# E-InkSmartMonitor.net
KiCad netlist of a schematic drawn in EAGLE
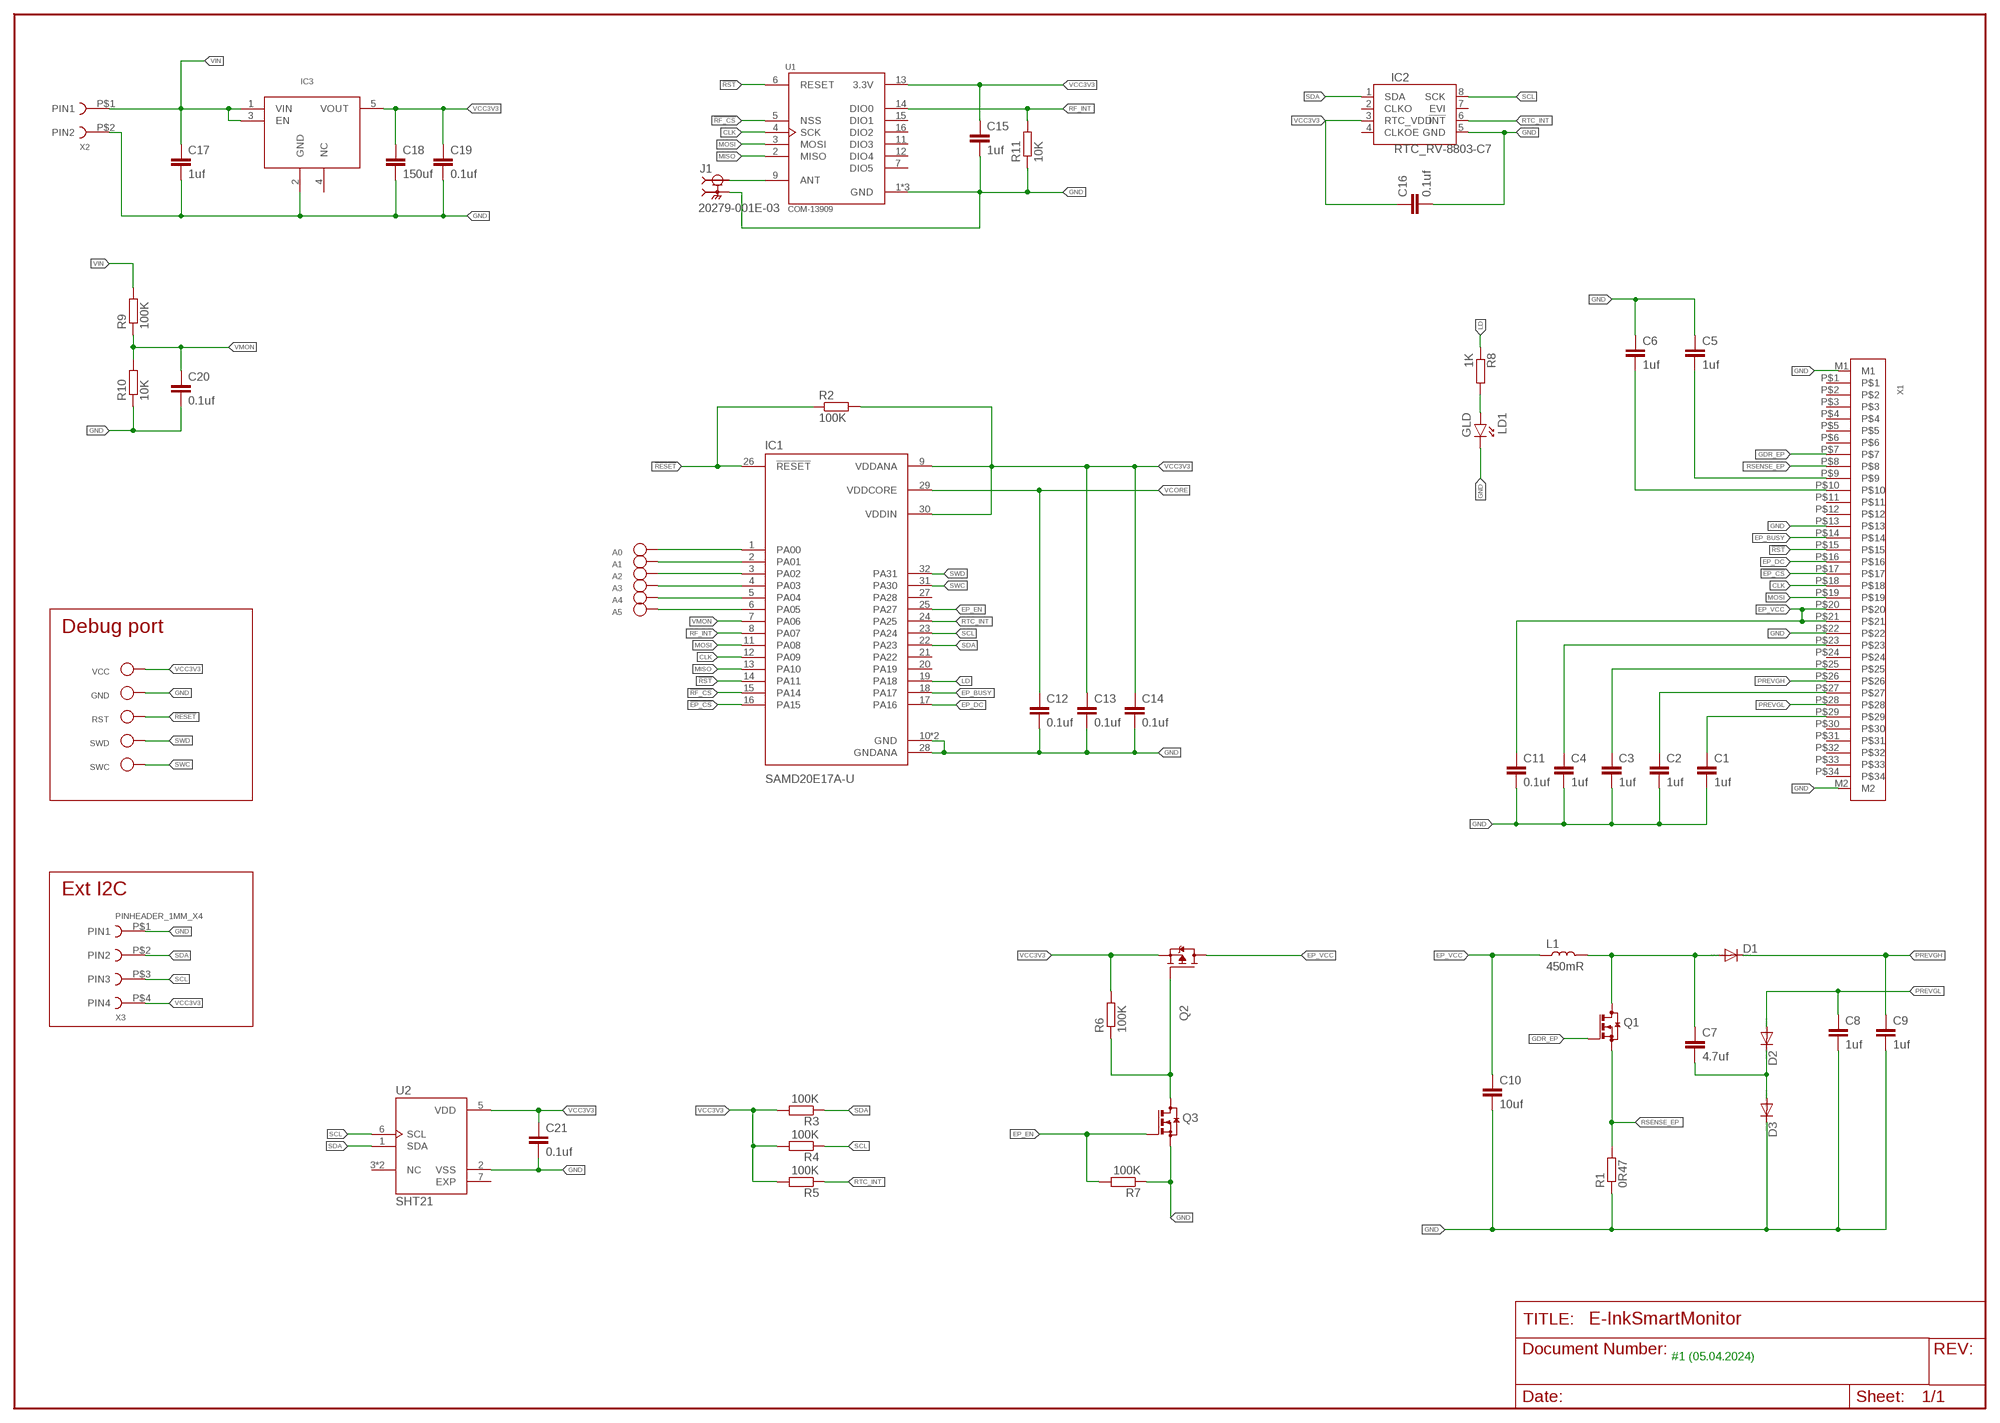
[diagram p0: schematic, sheet 1]

(export (version "E")
  (design (tool "Eeschema 10.0.6"))
  (components
    (comp (ref "A0")
      (value "TEST_POINT_D2MM")
      (footprint "eagle-import:TP")
      (libsource (lib "eagle-import") (part "TEST_POINT_D2MM"))
    )
    (comp (ref "A1")
      (value "TEST_POINT_D2MM")
      (footprint "eagle-import:TP")
      (libsource (lib "eagle-import") (part "TEST_POINT_D2MM"))
    )
    (comp (ref "A2")
      (value "TEST_POINT_D2MM")
      (footprint "eagle-import:TP")
      (libsource (lib "eagle-import") (part "TEST_POINT_D2MM"))
    )
    (comp (ref "A3")
      (value "TEST_POINT_D2MM")
      (footprint "eagle-import:TP")
      (libsource (lib "eagle-import") (part "TEST_POINT_D2MM"))
    )
    (comp (ref "A4")
      (value "TEST_POINT_D2MM")
      (footprint "eagle-import:TP")
      (libsource (lib "eagle-import") (part "TEST_POINT_D2MM"))
    )
    (comp (ref "A5")
      (value "TEST_POINT_D2MM")
      (footprint "eagle-import:TP")
      (libsource (lib "eagle-import") (part "TEST_POINT_D2MM"))
    )
    (comp (ref "C1")
      (value "1uf")
      (footprint "eagle-import:0805")
      (libsource (lib "eagle-import") (part "SMD_C0805"))
    )
    (comp (ref "C2")
      (value "1uf")
      (footprint "eagle-import:0805")
      (libsource (lib "eagle-import") (part "SMD_C0805"))
    )
    (comp (ref "C3")
      (value "1uf")
      (footprint "eagle-import:0805")
      (libsource (lib "eagle-import") (part "SMD_C0805"))
    )
    (comp (ref "C4")
      (value "1uf")
      (footprint "eagle-import:0805")
      (libsource (lib "eagle-import") (part "SMD_C0805"))
    )
    (comp (ref "C5")
      (value "1uf")
      (footprint "eagle-import:0805")
      (libsource (lib "eagle-import") (part "SMD_C0805"))
    )
    (comp (ref "C6")
      (value "1uf")
      (footprint "eagle-import:0805")
      (libsource (lib "eagle-import") (part "SMD_C0805"))
    )
    (comp (ref "C7")
      (value "4.7uf")
      (footprint "eagle-import:0805")
      (libsource (lib "eagle-import") (part "SMD_C0805"))
    )
    (comp (ref "C8")
      (value "1uf")
      (footprint "eagle-import:0805")
      (libsource (lib "eagle-import") (part "SMD_C0805"))
    )
    (comp (ref "C9")
      (value "1uf")
      (footprint "eagle-import:0805")
      (libsource (lib "eagle-import") (part "SMD_C0805"))
    )
    (comp (ref "C10")
      (value "10uf")
      (footprint "eagle-import:0805")
      (libsource (lib "eagle-import") (part "SMD_C0805"))
    )
    (comp (ref "C11")
      (value "0.1uf")
      (footprint "eagle-import:0603")
      (libsource (lib "eagle-import") (part "SMD_C0603"))
    )
    (comp (ref "C12")
      (value "0.1uf")
      (footprint "eagle-import:0603")
      (libsource (lib "eagle-import") (part "SMD_C0603"))
    )
    (comp (ref "C13")
      (value "0.1uf")
      (footprint "eagle-import:0603")
      (libsource (lib "eagle-import") (part "SMD_C0603"))
    )
    (comp (ref "C14")
      (value "0.1uf")
      (footprint "eagle-import:0603")
      (libsource (lib "eagle-import") (part "SMD_C0603"))
    )
    (comp (ref "C15")
      (value "1uf")
      (footprint "eagle-import:0805")
      (libsource (lib "eagle-import") (part "SMD_C0805"))
    )
    (comp (ref "C16")
      (value "0.1uf")
      (footprint "eagle-import:0603")
      (libsource (lib "eagle-import") (part "SMD_C0603"))
    )
    (comp (ref "C17")
      (value "1uf")
      (footprint "eagle-import:0805")
      (libsource (lib "eagle-import") (part "SMD_C0805"))
    )
    (comp (ref "C18")
      (value "150uf")
      (footprint "eagle-import:0805")
      (libsource (lib "eagle-import") (part "SMD_C0805"))
    )
    (comp (ref "C19")
      (value "0.1uf")
      (footprint "eagle-import:0603")
      (libsource (lib "eagle-import") (part "SMD_C0603"))
    )
    (comp (ref "C20")
      (value "0.1uf")
      (footprint "eagle-import:0603")
      (libsource (lib "eagle-import") (part "SMD_C0603"))
    )
    (comp (ref "C21")
      (value "0.1uf")
      (footprint "eagle-import:0603")
      (libsource (lib "eagle-import") (part "SMD_C0603"))
    )
    (comp (ref "D1")
      (value "DIODE-SOD323-R")
      (footprint "eagle-import:SOD323-R")
      (libsource (lib "eagle-import") (part "DIODE-SOD323-R"))
    )
    (comp (ref "D2")
      (value "DIODE-SOD323-R")
      (footprint "eagle-import:SOD323-R")
      (libsource (lib "eagle-import") (part "DIODE-SOD323-R"))
    )
    (comp (ref "D3")
      (value "DIODE-SOD323-R")
      (footprint "eagle-import:SOD323-R")
      (libsource (lib "eagle-import") (part "DIODE-SOD323-R"))
    )
    (comp (ref "GND")
      (value "TEST_POINT_D2MM")
      (footprint "eagle-import:TP")
      (libsource (lib "eagle-import") (part "TEST_POINT_D2MM"))
    )
    (comp (ref "IC1")
      (value "SAMD20E17A-U")
      (footprint "eagle-import:MLF32-TH")
      (libsource (lib "eagle-import") (part "SAMD20E17A-U"))
    )
    (comp (ref "IC2")
      (value "RTC_RV-8803-C7")
      (footprint "eagle-import:C7_RTC")
      (libsource (lib "eagle-import") (part "RTC_RV-8803-C7"))
    )
    (comp (ref "IC3")
      (value "LDO_3.3V_SOT23(5)")
      (footprint "eagle-import:SOT-23(5)")
      (libsource (lib "eagle-import") (part "LDO_3.3V_SOT23(5)"))
    )
    (comp (ref "J1")
      (value "20279-001E-03")
      (footprint "eagle-import:IPEX_20279-001E-03")
      (fields (field (name "MF") "I-PEX"))
      (libsource (lib "eagle-import") (part "20279-001E-03"))
    )
    (comp (ref "L1")
      (value "450mR")
      (footprint "eagle-import:3232")
      (libsource (lib "eagle-import") (part "SMD_L3232"))
    )
    (comp (ref "LD1")
      (value "GLD")
      (footprint "eagle-import:0603_P")
      (libsource (lib "eagle-import") (part "LED0603"))
    )
    (comp (ref "Q1")
      (value "BSS123SOT-23-3")
      (footprint "eagle-import:SOT-23(3)")
      (libsource (lib "eagle-import") (part "BSS123SOT-23-3"))
    )
    (comp (ref "Q2")
      (value "P_CH_SOT23SOT-23-3")
      (footprint "eagle-import:SOT-23(3)")
      (libsource (lib "eagle-import") (part "P_CH_SOT23SOT-23-3"))
    )
    (comp (ref "Q3")
      (value "BSS123SOT-23-3")
      (footprint "eagle-import:SOT-23(3)")
      (libsource (lib "eagle-import") (part "BSS123SOT-23-3"))
    )
    (comp (ref "R1")
      (value "0R47")
      (footprint "eagle-import:0603")
      (libsource (lib "eagle-import") (part "SMD_R0603"))
    )
    (comp (ref "R2")
      (value "100K")
      (footprint "eagle-import:0603")
      (libsource (lib "eagle-import") (part "SMD_R0603"))
    )
    (comp (ref "R3")
      (value "100K")
      (footprint "eagle-import:0603")
      (libsource (lib "eagle-import") (part "SMD_R0603"))
    )
    (comp (ref "R4")
      (value "100K")
      (footprint "eagle-import:0603")
      (libsource (lib "eagle-import") (part "SMD_R0603"))
    )
    (comp (ref "R5")
      (value "100K")
      (footprint "eagle-import:0603")
      (libsource (lib "eagle-import") (part "SMD_R0603"))
    )
    (comp (ref "R6")
      (value "100K")
      (footprint "eagle-import:0603")
      (libsource (lib "eagle-import") (part "SMD_R0603"))
    )
    (comp (ref "R7")
      (value "100K")
      (footprint "eagle-import:0603")
      (libsource (lib "eagle-import") (part "SMD_R0603"))
    )
    (comp (ref "R8")
      (value "1K")
      (footprint "eagle-import:0603")
      (libsource (lib "eagle-import") (part "SMD_R0603"))
    )
    (comp (ref "R9")
      (value "100K")
      (footprint "eagle-import:0603")
      (libsource (lib "eagle-import") (part "SMD_R0603"))
    )
    (comp (ref "R10")
      (value "10K")
      (footprint "eagle-import:0603")
      (libsource (lib "eagle-import") (part "SMD_R0603"))
    )
    (comp (ref "R11")
      (value "10K")
      (footprint "eagle-import:0603")
      (libsource (lib "eagle-import") (part "SMD_R0603"))
    )
    (comp (ref "RST")
      (value "TEST_POINT_D2MM")
      (footprint "eagle-import:TP")
      (libsource (lib "eagle-import") (part "TEST_POINT_D2MM"))
    )
    (comp (ref "SWC")
      (value "TEST_POINT_D2MM")
      (footprint "eagle-import:TP")
      (libsource (lib "eagle-import") (part "TEST_POINT_D2MM"))
    )
    (comp (ref "SWD")
      (value "TEST_POINT_D2MM")
      (footprint "eagle-import:TP")
      (libsource (lib "eagle-import") (part "TEST_POINT_D2MM"))
    )
    (comp (ref "U1")
      (value "COM-13909")
      (footprint "eagle-import:MOD_COM-13909")
      (fields (field (name "MF") "HOPERF") (field (name "MP") "RFM69HCW-315S2"))
      (libsource (lib "eagle-import") (part "COM-13909"))
    )
    (comp (ref "U2")
      (value "SHT21")
      (footprint "eagle-import:XDCR_SHT21")
      (fields (field (name "MF") "Sensirion AG"))
      (libsource (lib "eagle-import") (part "SHT21"))
    )
    (comp (ref "VCC")
      (value "TEST_POINT_D2MM")
      (footprint "eagle-import:TP")
      (libsource (lib "eagle-import") (part "TEST_POINT_D2MM"))
    )
    (comp (ref "X1")
      (value "FFC_3405EINK")
      (footprint "eagle-import:FFC_3405EINK")
      (libsource (lib "eagle-import") (part "FFC_3405EINK"))
    )
    (comp (ref "X2")
      (value "PINHEADER_1MM_X22X_1MM_PIN")
      (footprint "eagle-import:PIN_1MM_X2")
      (libsource (lib "eagle-import") (part "PINHEADER_1MM_X22X_1MM_PIN"))
    )
    (comp (ref "X3")
      (value "PINHEADER_1MM_X4")
      (footprint "eagle-import:PIN_1MM_X4")
      (libsource (lib "eagle-import") (part "PINHEADER_1MM_X4"))
    )
  )
  (nets
    (net (code "1") (name "/~{EP_CS}") (class "Default")
      (node (ref "IC1") (pin "16") (pinfunction "PA15_16") (pintype "bidirectional"))
      (node (ref "X1") (pin "P$17") (pinfunction "P$17_P$17") (pintype "bidirectional"))
    )
    (net (code "2") (name "/~{RESET}") (class "Default")
      (node (ref "IC1") (pin "26") (pinfunction "~{RESET}_26") (pintype "input"))
      (node (ref "R2") (pin "1") (pinfunction "1_1") (pintype "passive"))
      (node (ref "RST") (pin "P$1") (pinfunction "1_P$1") (pintype "bidirectional"))
    )
    (net (code "3") (name "/~{RF_CS}") (class "Default")
      (node (ref "IC1") (pin "15") (pinfunction "PA14_15") (pintype "bidirectional"))
      (node (ref "U1") (pin "5") (pinfunction "NSS_5") (pintype "input"))
    )
    (net (code "4") (name "/~{RST}") (class "Default")
      (node (ref "IC1") (pin "14") (pinfunction "PA11_14") (pintype "bidirectional"))
      (node (ref "U1") (pin "6") (pinfunction "RESET_6") (pintype "bidirectional"))
      (node (ref "X1") (pin "P$15") (pinfunction "P$15_P$15") (pintype "bidirectional"))
    )
    (net (code "5") (name "CLK") (class "Default")
      (node (ref "IC1") (pin "12") (pinfunction "PA09_12") (pintype "bidirectional"))
      (node (ref "U1") (pin "4") (pinfunction "SCK_4") (pintype "input"))
      (node (ref "X1") (pin "P$18") (pinfunction "P$18_P$18") (pintype "bidirectional"))
    )
    (net (code "6") (name "EP_BUSY") (class "Default")
      (node (ref "IC1") (pin "18") (pinfunction "PA17_18") (pintype "bidirectional"))
      (node (ref "X1") (pin "P$14") (pinfunction "P$14_P$14") (pintype "bidirectional"))
    )
    (net (code "7") (name "EP_DC") (class "Default")
      (node (ref "IC1") (pin "17") (pinfunction "PA16_17") (pintype "bidirectional"))
      (node (ref "X1") (pin "P$16") (pinfunction "P$16_P$16") (pintype "bidirectional"))
    )
    (net (code "8") (name "EP_EN") (class "Default")
      (node (ref "IC1") (pin "25") (pinfunction "PA27_25") (pintype "bidirectional"))
      (node (ref "Q3") (pin "1") (pinfunction "G_1") (pintype "passive"))
      (node (ref "R7") (pin "2") (pinfunction "2_2") (pintype "passive"))
    )
    (net (code "9") (name "EP_VCC") (class "Default")
      (node (ref "C10") (pin "1") (pinfunction "1_1") (pintype "passive"))
      (node (ref "C11") (pin "1") (pinfunction "1_1") (pintype "passive"))
      (node (ref "L1") (pin "M") (pinfunction "1_M") (pintype "passive"))
      (node (ref "Q2") (pin "3") (pinfunction "D_3") (pintype "passive"))
      (node (ref "X1") (pin "P$20") (pinfunction "P$20_P$20") (pintype "bidirectional"))
      (node (ref "X1") (pin "P$21") (pinfunction "P$21_P$21") (pintype "bidirectional"))
    )
    (net (code "10") (name "GDR_EP") (class "Default")
      (node (ref "Q1") (pin "1") (pinfunction "G_1") (pintype "passive"))
      (node (ref "X1") (pin "P$7") (pinfunction "P$7_P$7") (pintype "bidirectional"))
    )
    (net (code "11") (name "GND") (class "Default")
      (node (ref "C1") (pin "2") (pinfunction "2_2") (pintype "passive"))
      (node (ref "C10") (pin "2") (pinfunction "2_2") (pintype "passive"))
      (node (ref "C11") (pin "2") (pinfunction "2_2") (pintype "passive"))
      (node (ref "C12") (pin "2") (pinfunction "2_2") (pintype "passive"))
      (node (ref "C13") (pin "2") (pinfunction "2_2") (pintype "passive"))
      (node (ref "C14") (pin "2") (pinfunction "2_2") (pintype "passive"))
      (node (ref "C15") (pin "2") (pinfunction "2_2") (pintype "passive"))
      (node (ref "C16") (pin "2") (pinfunction "2_2") (pintype "passive"))
      (node (ref "C17") (pin "2") (pinfunction "2_2") (pintype "passive"))
      (node (ref "C18") (pin "2") (pinfunction "2_2") (pintype "passive"))
      (node (ref "C19") (pin "2") (pinfunction "2_2") (pintype "passive"))
      (node (ref "C2") (pin "2") (pinfunction "2_2") (pintype "passive"))
      (node (ref "C20") (pin "2") (pinfunction "2_2") (pintype "passive"))
      (node (ref "C21") (pin "2") (pinfunction "2_2") (pintype "passive"))
      (node (ref "C3") (pin "2") (pinfunction "2_2") (pintype "passive"))
      (node (ref "C4") (pin "2") (pinfunction "2_2") (pintype "passive"))
      (node (ref "C5") (pin "1") (pinfunction "1_1") (pintype "passive"))
      (node (ref "C6") (pin "1") (pinfunction "1_1") (pintype "passive"))
      (node (ref "C8") (pin "2") (pinfunction "2_2") (pintype "passive"))
      (node (ref "C9") (pin "2") (pinfunction "2_2") (pintype "passive"))
      (node (ref "D3") (pin "C") (pinfunction "C_C") (pintype "passive"))
      (node (ref "GND") (pin "P$1") (pinfunction "1_P$1") (pintype "bidirectional"))
      (node (ref "IC1") (pin "10") (pinfunction "GND_10") (pintype "power_in"))
      (node (ref "IC1") (pin "28") (pinfunction "GNDANA_28") (pintype "power_in"))
      (node (ref "IC1") (pin "TH") (pinfunction "GND_TH") (pintype "power_in"))
      (node (ref "IC2") (pin "5") (pinfunction "GND_5") (pintype "bidirectional"))
      (node (ref "IC3") (pin "2") (pinfunction "GND_2") (pintype "bidirectional"))
      (node (ref "J1") (pin "2") (pinfunction "GND_2") (pintype "passive"))
      (node (ref "J1") (pin "3") (pinfunction "GND_3") (pintype "passive"))
      (node (ref "LD1") (pin "1") (pinfunction "K_1") (pintype "bidirectional"))
      (node (ref "Q3") (pin "2") (pinfunction "S_2") (pintype "passive"))
      (node (ref "R1") (pin "1") (pinfunction "1_1") (pintype "passive"))
      (node (ref "R10") (pin "1") (pinfunction "1_1") (pintype "passive"))
      (node (ref "R11") (pin "1") (pinfunction "1_1") (pintype "passive"))
      (node (ref "R7") (pin "1") (pinfunction "1_1") (pintype "passive"))
      (node (ref "U1") (pin "1") (pinfunction "GND_1") (pintype "power_in"))
      (node (ref "U1") (pin "10") (pinfunction "GND_10") (pintype "power_in"))
      (node (ref "U1") (pin "8") (pinfunction "GND_8") (pintype "power_in"))
      (node (ref "U2") (pin "2") (pinfunction "VSS_2") (pintype "power_in"))
      (node (ref "X1") (pin "M1") (pinfunction "M1_M1") (pintype "bidirectional"))
      (node (ref "X1") (pin "M2") (pinfunction "M2_M2") (pintype "bidirectional"))
      (node (ref "X1") (pin "P$13") (pinfunction "P$13_P$13") (pintype "bidirectional"))
      (node (ref "X1") (pin "P$22") (pinfunction "P$22_P$22") (pintype "bidirectional"))
      (node (ref "X2") (pin "P$2") (pinfunction "PIN2_P$2") (pintype "bidirectional"))
      (node (ref "X3") (pin "P$1") (pinfunction "PIN1_P$1") (pintype "bidirectional"))
    )
    (net (code "12") (name "LD") (class "Default")
      (node (ref "IC1") (pin "19") (pinfunction "PA18_19") (pintype "bidirectional"))
      (node (ref "R8") (pin "1") (pinfunction "1_1") (pintype "passive"))
    )
    (net (code "13") (name "MISO") (class "Default")
      (node (ref "IC1") (pin "13") (pinfunction "PA10_13") (pintype "bidirectional"))
      (node (ref "U1") (pin "2") (pinfunction "MISO_2") (pintype "input"))
    )
    (net (code "14") (name "MOSI") (class "Default")
      (node (ref "IC1") (pin "11") (pinfunction "PA08_11") (pintype "bidirectional"))
      (node (ref "U1") (pin "3") (pinfunction "MOSI_3") (pintype "output"))
      (node (ref "X1") (pin "P$19") (pinfunction "P$19_P$19") (pintype "bidirectional"))
    )
    (net (code "15") (name "Net-(A0-1)") (class "Default")
      (node (ref "A0") (pin "P$1") (pinfunction "1_P$1") (pintype "bidirectional"))
      (node (ref "IC1") (pin "1") (pinfunction "PA00_1") (pintype "bidirectional"))
    )
    (net (code "16") (name "Net-(A1-1)") (class "Default")
      (node (ref "A1") (pin "P$1") (pinfunction "1_P$1") (pintype "bidirectional"))
      (node (ref "IC1") (pin "2") (pinfunction "PA01_2") (pintype "bidirectional"))
    )
    (net (code "17") (name "Net-(A2-1)") (class "Default")
      (node (ref "A2") (pin "P$1") (pinfunction "1_P$1") (pintype "bidirectional"))
      (node (ref "IC1") (pin "3") (pinfunction "PA02_3") (pintype "bidirectional"))
    )
    (net (code "18") (name "Net-(A3-1)") (class "Default")
      (node (ref "A3") (pin "P$1") (pinfunction "1_P$1") (pintype "bidirectional"))
      (node (ref "IC1") (pin "4") (pinfunction "PA03_4") (pintype "bidirectional"))
    )
    (net (code "19") (name "Net-(A4-1)") (class "Default")
      (node (ref "A4") (pin "P$1") (pinfunction "1_P$1") (pintype "bidirectional"))
      (node (ref "IC1") (pin "5") (pinfunction "PA04_5") (pintype "bidirectional"))
    )
    (net (code "20") (name "Net-(A5-1)") (class "Default")
      (node (ref "A5") (pin "P$1") (pinfunction "1_P$1") (pintype "bidirectional"))
      (node (ref "IC1") (pin "6") (pinfunction "PA05_6") (pintype "bidirectional"))
    )
    (net (code "21") (name "Net-(C1-Pad1)") (class "Default")
      (node (ref "C1") (pin "1") (pinfunction "1_1") (pintype "passive"))
      (node (ref "X1") (pin "P$29") (pinfunction "P$29_P$29") (pintype "bidirectional"))
    )
    (net (code "22") (name "Net-(C2-Pad1)") (class "Default")
      (node (ref "C2") (pin "1") (pinfunction "1_1") (pintype "passive"))
      (node (ref "X1") (pin "P$27") (pinfunction "P$27_P$27") (pintype "bidirectional"))
    )
    (net (code "23") (name "Net-(C3-Pad1)") (class "Default")
      (node (ref "C3") (pin "1") (pinfunction "1_1") (pintype "passive"))
      (node (ref "X1") (pin "P$25") (pinfunction "P$25_P$25") (pintype "bidirectional"))
    )
    (net (code "24") (name "Net-(C4-Pad1)") (class "Default")
      (node (ref "C4") (pin "1") (pinfunction "1_1") (pintype "passive"))
      (node (ref "X1") (pin "P$23") (pinfunction "P$23_P$23") (pintype "bidirectional"))
    )
    (net (code "25") (name "Net-(C5-Pad2)") (class "Default")
      (node (ref "C5") (pin "2") (pinfunction "2_2") (pintype "passive"))
      (node (ref "X1") (pin "P$9") (pinfunction "P$9_P$9") (pintype "bidirectional"))
    )
    (net (code "26") (name "Net-(C6-Pad2)") (class "Default")
      (node (ref "C6") (pin "2") (pinfunction "2_2") (pintype "passive"))
      (node (ref "X1") (pin "P$10") (pinfunction "P$10_P$10") (pintype "bidirectional"))
    )
    (net (code "27") (name "Net-(C7-Pad2)") (class "Default")
      (node (ref "C7") (pin "2") (pinfunction "2_2") (pintype "passive"))
      (node (ref "D2") (pin "C") (pinfunction "C_C") (pintype "passive"))
      (node (ref "D3") (pin "A") (pinfunction "A_A") (pintype "passive"))
    )
    (net (code "28") (name "Net-(J1-SIG)") (class "Default")
      (node (ref "J1") (pin "1") (pinfunction "SIG_1") (pintype "passive"))
      (node (ref "U1") (pin "9") (pinfunction "ANT_9") (pintype "bidirectional"))
    )
    (net (code "29") (name "Net-(L1-2)") (class "Default")
      (node (ref "C7") (pin "1") (pinfunction "1_1") (pintype "passive"))
      (node (ref "D1") (pin "A") (pinfunction "A_A") (pintype "passive"))
      (node (ref "L1") (pin "P") (pinfunction "2_P") (pintype "passive"))
      (node (ref "Q1") (pin "3") (pinfunction "D_3") (pintype "passive"))
    )
    (net (code "30") (name "Net-(LD1-A)") (class "Default")
      (node (ref "LD1") (pin "2") (pinfunction "A_2") (pintype "bidirectional"))
      (node (ref "R8") (pin "2") (pinfunction "2_2") (pintype "passive"))
    )
    (net (code "31") (name "Net-(Q2-G)") (class "Default")
      (node (ref "Q2") (pin "1") (pinfunction "G_1") (pintype "passive"))
      (node (ref "Q3") (pin "3") (pinfunction "D_3") (pintype "passive"))
      (node (ref "R6") (pin "1") (pinfunction "1_1") (pintype "passive"))
    )
    (net (code "32") (name "PREVGH") (class "Default")
      (node (ref "C9") (pin "1") (pinfunction "1_1") (pintype "passive"))
      (node (ref "D1") (pin "C") (pinfunction "C_C") (pintype "passive"))
      (node (ref "X1") (pin "P$26") (pinfunction "P$26_P$26") (pintype "bidirectional"))
    )
    (net (code "33") (name "PREVGL") (class "Default")
      (node (ref "C8") (pin "1") (pinfunction "1_1") (pintype "passive"))
      (node (ref "D2") (pin "A") (pinfunction "A_A") (pintype "passive"))
      (node (ref "X1") (pin "P$28") (pinfunction "P$28_P$28") (pintype "bidirectional"))
    )
    (net (code "34") (name "RF_INT") (class "Default")
      (node (ref "IC1") (pin "8") (pinfunction "PA07_8") (pintype "bidirectional"))
      (node (ref "R11") (pin "2") (pinfunction "2_2") (pintype "passive"))
      (node (ref "U1") (pin "14") (pinfunction "DIO0_14") (pintype "bidirectional"))
    )
    (net (code "35") (name "RSENSE_EP") (class "Default")
      (node (ref "Q1") (pin "2") (pinfunction "S_2") (pintype "passive"))
      (node (ref "R1") (pin "2") (pinfunction "2_2") (pintype "passive"))
      (node (ref "X1") (pin "P$8") (pinfunction "P$8_P$8") (pintype "bidirectional"))
    )
    (net (code "36") (name "RTC_INT") (class "Default")
      (node (ref "IC1") (pin "24") (pinfunction "PA25_24") (pintype "bidirectional"))
      (node (ref "IC2") (pin "6") (pinfunction "~{INT}_6") (pintype "bidirectional"))
      (node (ref "R5") (pin "1") (pinfunction "1_1") (pintype "passive"))
    )
    (net (code "37") (name "SCL") (class "Default")
      (node (ref "IC1") (pin "23") (pinfunction "PA24_23") (pintype "bidirectional"))
      (node (ref "IC2") (pin "8") (pinfunction "SCK_8") (pintype "bidirectional"))
      (node (ref "R4") (pin "1") (pinfunction "1_1") (pintype "passive"))
      (node (ref "U2") (pin "6") (pinfunction "SCL_6") (pintype "input"))
      (node (ref "X3") (pin "P$3") (pinfunction "PIN3_P$3") (pintype "bidirectional"))
    )
    (net (code "38") (name "SDA") (class "Default")
      (node (ref "IC1") (pin "22") (pinfunction "PA23_22") (pintype "bidirectional"))
      (node (ref "IC2") (pin "1") (pinfunction "SDA_1") (pintype "bidirectional"))
      (node (ref "R3") (pin "1") (pinfunction "1_1") (pintype "passive"))
      (node (ref "U2") (pin "1") (pinfunction "SDA_1") (pintype "bidirectional"))
      (node (ref "X3") (pin "P$2") (pinfunction "PIN2_P$2") (pintype "bidirectional"))
    )
    (net (code "39") (name "SWC") (class "Default")
      (node (ref "IC1") (pin "31") (pinfunction "PA30_31") (pintype "bidirectional"))
      (node (ref "SWC") (pin "P$1") (pinfunction "1_P$1") (pintype "bidirectional"))
    )
    (net (code "40") (name "SWD") (class "Default")
      (node (ref "IC1") (pin "32") (pinfunction "PA31_32") (pintype "bidirectional"))
      (node (ref "SWD") (pin "P$1") (pinfunction "1_P$1") (pintype "bidirectional"))
    )
    (net (code "41") (name "VCC3V3") (class "Default")
      (node (ref "C13") (pin "1") (pinfunction "1_1") (pintype "passive"))
      (node (ref "C14") (pin "1") (pinfunction "1_1") (pintype "passive"))
      (node (ref "C15") (pin "1") (pinfunction "1_1") (pintype "passive"))
      (node (ref "C16") (pin "1") (pinfunction "1_1") (pintype "passive"))
      (node (ref "C18") (pin "1") (pinfunction "1_1") (pintype "passive"))
      (node (ref "C19") (pin "1") (pinfunction "1_1") (pintype "passive"))
      (node (ref "C21") (pin "1") (pinfunction "1_1") (pintype "passive"))
      (node (ref "IC1") (pin "30") (pinfunction "VDDIN_30") (pintype "power_in"))
      (node (ref "IC1") (pin "9") (pinfunction "VDDANA_9") (pintype "power_in"))
      (node (ref "IC2") (pin "3") (pinfunction "RTC_VDD_3") (pintype "bidirectional"))
      (node (ref "IC3") (pin "5") (pinfunction "VOUT_5") (pintype "bidirectional"))
      (node (ref "Q2") (pin "2") (pinfunction "S_2") (pintype "passive"))
      (node (ref "R2") (pin "2") (pinfunction "2_2") (pintype "passive"))
      (node (ref "R3") (pin "2") (pinfunction "2_2") (pintype "passive"))
      (node (ref "R4") (pin "2") (pinfunction "2_2") (pintype "passive"))
      (node (ref "R5") (pin "2") (pinfunction "2_2") (pintype "passive"))
      (node (ref "R6") (pin "2") (pinfunction "2_2") (pintype "passive"))
      (node (ref "U1") (pin "13") (pinfunction "3.3V_13") (pintype "power_in"))
      (node (ref "U2") (pin "5") (pinfunction "VDD_5") (pintype "power_in"))
      (node (ref "VCC") (pin "P$1") (pinfunction "1_P$1") (pintype "bidirectional"))
      (node (ref "X3") (pin "P$4") (pinfunction "PIN4_P$4") (pintype "bidirectional"))
    )
    (net (code "42") (name "VCORE") (class "Default")
      (node (ref "C12") (pin "1") (pinfunction "1_1") (pintype "passive"))
      (node (ref "IC1") (pin "29") (pinfunction "VDDCORE_29") (pintype "power_in"))
    )
    (net (code "43") (name "VIN") (class "Default")
      (node (ref "C17") (pin "1") (pinfunction "1_1") (pintype "passive"))
      (node (ref "IC3") (pin "1") (pinfunction "VIN_1") (pintype "bidirectional"))
      (node (ref "IC3") (pin "3") (pinfunction "EN_3") (pintype "bidirectional"))
      (node (ref "R9") (pin "2") (pinfunction "2_2") (pintype "passive"))
      (node (ref "X2") (pin "P$1") (pinfunction "PIN1_P$1") (pintype "bidirectional"))
    )
    (net (code "44") (name "VMON") (class "Default")
      (node (ref "C20") (pin "1") (pinfunction "1_1") (pintype "passive"))
      (node (ref "IC1") (pin "7") (pinfunction "PA06_7") (pintype "bidirectional"))
      (node (ref "R10") (pin "2") (pinfunction "2_2") (pintype "passive"))
      (node (ref "R9") (pin "1") (pinfunction "1_1") (pintype "passive"))
    )
    (net (code "45") (name "unconnected-(IC1-PA19-Pad20)") (class "Default")
      (node (ref "IC1") (pin "20") (pinfunction "PA19_20") (pintype "bidirectional"))
    )
    (net (code "46") (name "unconnected-(IC1-PA22-Pad21)") (class "Default")
      (node (ref "IC1") (pin "21") (pinfunction "PA22_21") (pintype "bidirectional"))
    )
    (net (code "47") (name "unconnected-(IC1-PA28-Pad27)") (class "Default")
      (node (ref "IC1") (pin "27") (pinfunction "PA28_27") (pintype "bidirectional"))
    )
    (net (code "48") (name "unconnected-(IC2-CLKO-Pad2)") (class "Default")
      (node (ref "IC2") (pin "2") (pinfunction "CLKO_2") (pintype "bidirectional"))
    )
    (net (code "49") (name "unconnected-(IC2-CLKOE-Pad4)") (class "Default")
      (node (ref "IC2") (pin "4") (pinfunction "CLKOE_4") (pintype "bidirectional"))
    )
    (net (code "50") (name "unconnected-(IC2-EVI-Pad7)") (class "Default")
      (node (ref "IC2") (pin "7") (pinfunction "EVI_7") (pintype "bidirectional"))
    )
    (net (code "51") (name "unconnected-(IC3-NC-Pad4)") (class "Default")
      (node (ref "IC3") (pin "4") (pinfunction "NC_4") (pintype "bidirectional"))
    )
    (net (code "52") (name "unconnected-(U1-DIO1-Pad15)") (class "Default")
      (node (ref "U1") (pin "15") (pinfunction "DIO1_15") (pintype "bidirectional"))
    )
    (net (code "53") (name "unconnected-(U1-DIO2-Pad16)") (class "Default")
      (node (ref "U1") (pin "16") (pinfunction "DIO2_16") (pintype "bidirectional"))
    )
    (net (code "54") (name "unconnected-(U1-DIO3-Pad11)") (class "Default")
      (node (ref "U1") (pin "11") (pinfunction "DIO3_11") (pintype "bidirectional"))
    )
    (net (code "55") (name "unconnected-(U1-DIO4-Pad12)") (class "Default")
      (node (ref "U1") (pin "12") (pinfunction "DIO4_12") (pintype "bidirectional"))
    )
    (net (code "56") (name "unconnected-(U1-DIO5-Pad7)") (class "Default")
      (node (ref "U1") (pin "7") (pinfunction "DIO5_7") (pintype "bidirectional"))
    )
    (net (code "57") (name "unconnected-(U2-EXP-Pad7)") (class "Default")
      (node (ref "U2") (pin "7") (pinfunction "EXP_7") (pintype "passive"))
    )
    (net (code "58") (name "unconnected-(U2-NC-Pad3)") (class "Default")
      (node (ref "U2") (pin "3") (pinfunction "NC_3") (pintype "no_connect"))
    )
    (net (code "59") (name "unconnected-(U2-NC-Pad4)") (class "Default")
      (node (ref "U2") (pin "4") (pinfunction "NC_4") (pintype "no_connect"))
    )
    (net (code "60") (name "unconnected-(X1-PadP$1)") (class "Default")
      (node (ref "X1") (pin "P$1") (pinfunction "P$1_P$1") (pintype "bidirectional"))
    )
    (net (code "61") (name "unconnected-(X1-PadP$2)") (class "Default")
      (node (ref "X1") (pin "P$2") (pinfunction "P$2_P$2") (pintype "bidirectional"))
    )
    (net (code "62") (name "unconnected-(X1-PadP$3)") (class "Default")
      (node (ref "X1") (pin "P$3") (pinfunction "P$3_P$3") (pintype "bidirectional"))
    )
    (net (code "63") (name "unconnected-(X1-PadP$4)") (class "Default")
      (node (ref "X1") (pin "P$4") (pinfunction "P$4_P$4") (pintype "bidirectional"))
    )
    (net (code "64") (name "unconnected-(X1-PadP$5)") (class "Default")
      (node (ref "X1") (pin "P$5") (pinfunction "P$5_P$5") (pintype "bidirectional"))
    )
    (net (code "65") (name "unconnected-(X1-PadP$6)") (class "Default")
      (node (ref "X1") (pin "P$6") (pinfunction "P$6_P$6") (pintype "bidirectional"))
    )
    (net (code "66") (name "unconnected-(X1-PadP$11)") (class "Default")
      (node (ref "X1") (pin "P$11") (pinfunction "P$11_P$11") (pintype "bidirectional"))
    )
    (net (code "67") (name "unconnected-(X1-PadP$12)") (class "Default")
      (node (ref "X1") (pin "P$12") (pinfunction "P$12_P$12") (pintype "bidirectional"))
    )
    (net (code "68") (name "unconnected-(X1-PadP$24)") (class "Default")
      (node (ref "X1") (pin "P$24") (pinfunction "P$24_P$24") (pintype "bidirectional"))
    )
    (net (code "69") (name "unconnected-(X1-PadP$30)") (class "Default")
      (node (ref "X1") (pin "P$30") (pinfunction "P$30_P$30") (pintype "bidirectional"))
    )
    (net (code "70") (name "unconnected-(X1-PadP$31)") (class "Default")
      (node (ref "X1") (pin "P$31") (pinfunction "P$31_P$31") (pintype "bidirectional"))
    )
    (net (code "71") (name "unconnected-(X1-PadP$32)") (class "Default")
      (node (ref "X1") (pin "P$32") (pinfunction "P$32_P$32") (pintype "bidirectional"))
    )
    (net (code "72") (name "unconnected-(X1-PadP$33)") (class "Default")
      (node (ref "X1") (pin "P$33") (pinfunction "P$33_P$33") (pintype "bidirectional"))
    )
    (net (code "73") (name "unconnected-(X1-PadP$34)") (class "Default")
      (node (ref "X1") (pin "P$34") (pinfunction "P$34_P$34") (pintype "bidirectional"))
    )
  )
)
